# Servo.net
KiCad netlist of a schematic drawn in EAGLE
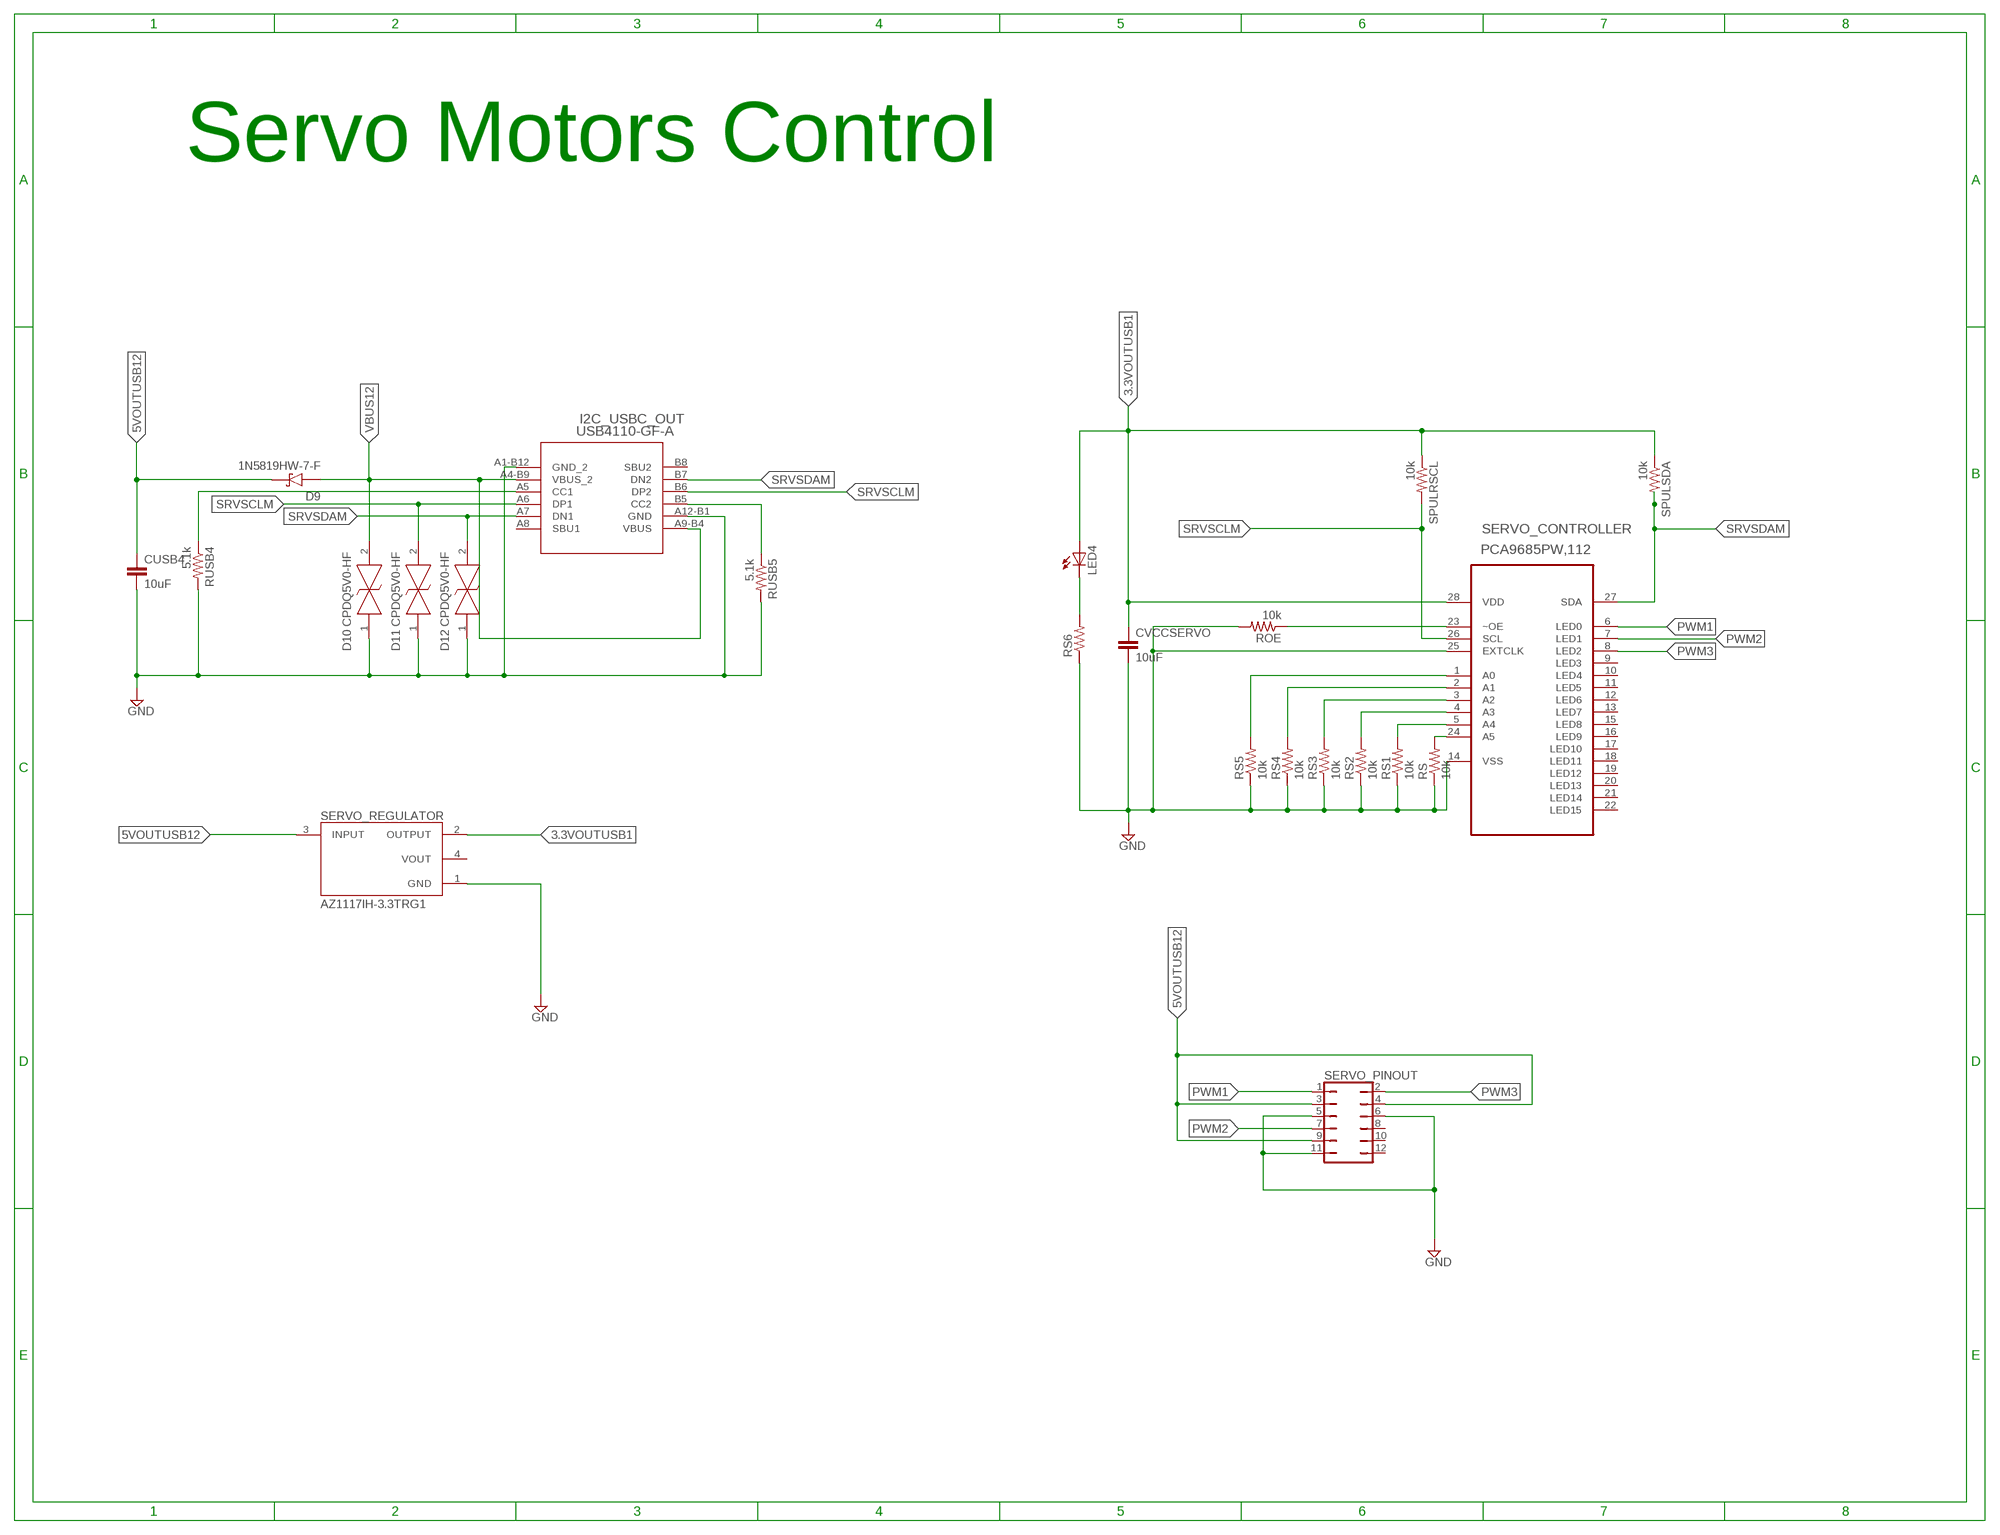
[diagram p0: schematic, sheet 1]

(export (version "E")
  (design (tool "Eeschema 10.0.6"))
  (components
    (comp (ref "CUSB4")
      (value "10uF")
      (footprint "eagle-import:C0805")
      (libsource (lib "eagle-import") (part "C-EUC0805"))
    )
    (comp (ref "CVCCSERVO")
      (value "10uF")
      (footprint "eagle-import:C0805")
      (libsource (lib "eagle-import") (part "C-EUC0805"))
    )
    (comp (ref "D9")
      (value "1N5819HW-7-F")
      (footprint "eagle-import:SOD3715X145N")
      (fields (field (name "MF") "Diodes Inc."))
      (libsource (lib "eagle-import") (part "1N5819HW-7-F"))
    )
    (comp (ref "D10")
      (value "CPDQ5V0-HF")
      (footprint "eagle-import:MBTB-D-SOD-923F-IMP-0402")
      (fields (field (name "MF") "Comchip Technology"))
      (libsource (lib "eagle-import") (part "CPDQ5V0-HF"))
    )
    (comp (ref "D11")
      (value "CPDQ5V0-HF")
      (footprint "eagle-import:MBTB-D-SOD-923F-IMP-0402")
      (fields (field (name "MF") "Comchip Technology"))
      (libsource (lib "eagle-import") (part "CPDQ5V0-HF"))
    )
    (comp (ref "D12")
      (value "CPDQ5V0-HF")
      (footprint "eagle-import:MBTB-D-SOD-923F-IMP-0402")
      (fields (field (name "MF") "Comchip Technology"))
      (libsource (lib "eagle-import") (part "CPDQ5V0-HF"))
    )
    (comp (ref "I2C_USBC_OUT")
      (value "USB4110-GF-A")
      (footprint "eagle-import:USB4110-GF-A_GCT")
      (fields (field (name "COPYRIGHT") "Copyright (C) 2023 Ultra Librarian. All rights reserved."))
      (libsource (lib "eagle-import") (part "USB4110-GF-A"))
    )
    (comp (ref "LED4")
      (value "LED")
      (footprint "eagle-import:SMARTLED-TTW")
      (libsource (lib "eagle-import") (part "LED"))
    )
    (comp (ref "ROE")
      (value "10k")
      (footprint "eagle-import:M0805")
      (libsource (lib "eagle-import") (part "R-US_M0805"))
    )
    (comp (ref "RS")
      (value "10k")
      (footprint "eagle-import:R0805")
      (libsource (lib "eagle-import") (part "R-US_R0805"))
    )
    (comp (ref "RS1")
      (value "10k")
      (footprint "eagle-import:R0805")
      (libsource (lib "eagle-import") (part "R-US_R0805"))
    )
    (comp (ref "RS2")
      (value "10k")
      (footprint "eagle-import:R0805")
      (libsource (lib "eagle-import") (part "R-US_R0805"))
    )
    (comp (ref "RS3")
      (value "10k")
      (footprint "eagle-import:R0805")
      (libsource (lib "eagle-import") (part "R-US_R0805"))
    )
    (comp (ref "RS4")
      (value "10k")
      (footprint "eagle-import:R0805")
      (libsource (lib "eagle-import") (part "R-US_R0805"))
    )
    (comp (ref "RS5")
      (value "10k")
      (footprint "eagle-import:R0805")
      (libsource (lib "eagle-import") (part "R-US_R0805"))
    )
    (comp (ref "RS6")
      (value "2.2k")
      (footprint "eagle-import:R0805")
      (libsource (lib "eagle-import") (part "R-US_R0805"))
    )
    (comp (ref "RUSB4")
      (value "5.1k")
      (footprint "eagle-import:M0805")
      (libsource (lib "eagle-import") (part "R-US_M0805"))
    )
    (comp (ref "RUSB5")
      (value "5.1k")
      (footprint "eagle-import:M0805")
      (libsource (lib "eagle-import") (part "R-US_M0805"))
    )
    (comp (ref "SERVO_CONTROLLER")
      (value "PCA9685PW,112")
      (footprint "eagle-import:SOP65P640X110-28N")
      (fields (field (name "MF") "NXP USA"))
      (libsource (lib "eagle-import") (part "PCA9685PW,112"))
    )
    (comp (ref "SERVO_PINOUT")
      (value "JP6Q")
      (footprint "eagle-import:JP6Q")
      (libsource (lib "eagle-import") (part "JP6Q"))
    )
    (comp (ref "SERVO_REGULATOR")
      (value "AZ1117IH-3.3TRG1")
      (footprint "eagle-import:SOT230P700X185-4N")
      (fields (field (name "MF") "Diodes Inc."))
      (libsource (lib "eagle-import") (part "AZ1117IH-3.3TRG1"))
    )
    (comp (ref "SPULRSCL")
      (value "10k")
      (footprint "eagle-import:M0805")
      (libsource (lib "eagle-import") (part "R-US_M0805"))
    )
    (comp (ref "SPULSDA")
      (value "10k")
      (footprint "eagle-import:M0805")
      (libsource (lib "eagle-import") (part "R-US_M0805"))
    )
  )
  (nets
    (net (code "1") (name "3.3VOUTUSB1") (class "Default")
      (node (ref "CVCCSERVO") (pin "1") (pinfunction "1_1") (pintype "passive"))
      (node (ref "LED4") (pin "A@1") (pinfunction "A_A@1") (pintype "passive"))
      (node (ref "SERVO_CONTROLLER") (pin "28") (pinfunction "VDD_28") (pintype "power_in"))
      (node (ref "SERVO_REGULATOR") (pin "2") (pinfunction "OUTPUT_2") (pintype "output"))
      (node (ref "SPULRSCL") (pin "1") (pinfunction "1_1") (pintype "passive"))
      (node (ref "SPULSDA") (pin "1") (pinfunction "1_1") (pintype "passive"))
    )
    (net (code "2") (name "5VOUTUSB12") (class "Default")
      (node (ref "CUSB4") (pin "1") (pinfunction "1_1") (pintype "passive"))
      (node (ref "D9") (pin "C") (pinfunction "K_C") (pintype "passive"))
      (node (ref "SERVO_PINOUT") (pin "3") (pinfunction "3_3") (pintype "passive"))
      (node (ref "SERVO_PINOUT") (pin "4") (pinfunction "4_4") (pintype "passive"))
      (node (ref "SERVO_PINOUT") (pin "9") (pinfunction "9_9") (pintype "passive"))
      (node (ref "SERVO_REGULATOR") (pin "3") (pinfunction "INPUT_3") (pintype "input"))
    )
    (net (code "3") (name "GND") (class "Default")
      (node (ref "CUSB4") (pin "2") (pinfunction "2_2") (pintype "passive"))
      (node (ref "CVCCSERVO") (pin "2") (pinfunction "2_2") (pintype "passive"))
      (node (ref "D10") (pin "1") (pinfunction "K_1") (pintype "bidirectional"))
      (node (ref "D11") (pin "1") (pinfunction "K_1") (pintype "bidirectional"))
      (node (ref "D12") (pin "1") (pinfunction "K_1") (pintype "bidirectional"))
      (node (ref "I2C_USBC_OUT") (pin "A1-B12") (pinfunction "GND_2_A1-B12") (pintype "passive"))
      (node (ref "I2C_USBC_OUT") (pin "A12-B1") (pinfunction "GND_A12-B1") (pintype "passive"))
      (node (ref "ROE") (pin "2") (pinfunction "2_2") (pintype "passive"))
      (node (ref "RS") (pin "1") (pinfunction "1_1") (pintype "passive"))
      (node (ref "RS1") (pin "1") (pinfunction "1_1") (pintype "passive"))
      (node (ref "RS2") (pin "1") (pinfunction "1_1") (pintype "passive"))
      (node (ref "RS3") (pin "1") (pinfunction "1_1") (pintype "passive"))
      (node (ref "RS4") (pin "1") (pinfunction "1_1") (pintype "passive"))
      (node (ref "RS5") (pin "1") (pinfunction "1_1") (pintype "passive"))
      (node (ref "RS6") (pin "1") (pinfunction "1_1") (pintype "passive"))
      (node (ref "RUSB4") (pin "2") (pinfunction "2_2") (pintype "passive"))
      (node (ref "RUSB5") (pin "2") (pinfunction "2_2") (pintype "passive"))
      (node (ref "SERVO_CONTROLLER") (pin "14") (pinfunction "VSS_14") (pintype "passive"))
      (node (ref "SERVO_CONTROLLER") (pin "25") (pinfunction "EXTCLK_25") (pintype "input"))
      (node (ref "SERVO_PINOUT") (pin "11") (pinfunction "11_11") (pintype "passive"))
      (node (ref "SERVO_PINOUT") (pin "5") (pinfunction "5_5") (pintype "passive"))
      (node (ref "SERVO_PINOUT") (pin "6") (pinfunction "6_6") (pintype "passive"))
      (node (ref "SERVO_REGULATOR") (pin "1") (pinfunction "GND_1") (pintype "power_in"))
    )
    (net (code "4") (name "Net-(I2C_USBC_OUT-CC1)") (class "Default")
      (node (ref "I2C_USBC_OUT") (pin "A5") (pinfunction "CC1_A5") (pintype "bidirectional"))
      (node (ref "RUSB4") (pin "1") (pinfunction "1_1") (pintype "passive"))
    )
    (net (code "5") (name "Net-(I2C_USBC_OUT-CC2)") (class "Default")
      (node (ref "I2C_USBC_OUT") (pin "B5") (pinfunction "CC2_B5") (pintype "bidirectional"))
      (node (ref "RUSB5") (pin "1") (pinfunction "1_1") (pintype "passive"))
    )
    (net (code "6") (name "Net-(LED4-C)") (class "Default")
      (node (ref "LED4") (pin "C@1") (pinfunction "C_C@1") (pintype "passive"))
      (node (ref "RS6") (pin "2") (pinfunction "2_2") (pintype "passive"))
    )
    (net (code "7") (name "Net-(SERVO_CONTROLLER-A0)") (class "Default")
      (node (ref "RS5") (pin "2") (pinfunction "2_2") (pintype "passive"))
      (node (ref "SERVO_CONTROLLER") (pin "1") (pinfunction "A0_1") (pintype "input"))
    )
    (net (code "8") (name "Net-(SERVO_CONTROLLER-A1)") (class "Default")
      (node (ref "RS4") (pin "2") (pinfunction "2_2") (pintype "passive"))
      (node (ref "SERVO_CONTROLLER") (pin "2") (pinfunction "A1_2") (pintype "input"))
    )
    (net (code "9") (name "Net-(SERVO_CONTROLLER-A2)") (class "Default")
      (node (ref "RS3") (pin "2") (pinfunction "2_2") (pintype "passive"))
      (node (ref "SERVO_CONTROLLER") (pin "3") (pinfunction "A2_3") (pintype "input"))
    )
    (net (code "10") (name "Net-(SERVO_CONTROLLER-A3)") (class "Default")
      (node (ref "RS2") (pin "2") (pinfunction "2_2") (pintype "passive"))
      (node (ref "SERVO_CONTROLLER") (pin "4") (pinfunction "A3_4") (pintype "input"))
    )
    (net (code "11") (name "Net-(SERVO_CONTROLLER-A4)") (class "Default")
      (node (ref "RS1") (pin "2") (pinfunction "2_2") (pintype "passive"))
      (node (ref "SERVO_CONTROLLER") (pin "5") (pinfunction "A4_5") (pintype "input"))
    )
    (net (code "12") (name "Net-(SERVO_CONTROLLER-A5)") (class "Default")
      (node (ref "RS") (pin "2") (pinfunction "2_2") (pintype "passive"))
      (node (ref "SERVO_CONTROLLER") (pin "24") (pinfunction "A5_24") (pintype "input"))
    )
    (net (code "13") (name "Net-(SERVO_CONTROLLER-~{OE})") (class "Default")
      (node (ref "ROE") (pin "1") (pinfunction "1_1") (pintype "passive"))
      (node (ref "SERVO_CONTROLLER") (pin "23") (pinfunction "~{OE}_23") (pintype "input"))
    )
    (net (code "14") (name "PWM1") (class "Default")
      (node (ref "SERVO_CONTROLLER") (pin "6") (pinfunction "LED0_6") (pintype "output"))
      (node (ref "SERVO_PINOUT") (pin "1") (pinfunction "1_1") (pintype "passive"))
    )
    (net (code "15") (name "PWM2") (class "Default")
      (node (ref "SERVO_CONTROLLER") (pin "7") (pinfunction "LED1_7") (pintype "output"))
      (node (ref "SERVO_PINOUT") (pin "7") (pinfunction "7_7") (pintype "passive"))
    )
    (net (code "16") (name "PWM3") (class "Default")
      (node (ref "SERVO_CONTROLLER") (pin "8") (pinfunction "LED2_8") (pintype "output"))
      (node (ref "SERVO_PINOUT") (pin "2") (pinfunction "2_2") (pintype "passive"))
    )
    (net (code "17") (name "SRVSCLM") (class "Default")
      (node (ref "D11") (pin "2") (pinfunction "A_2") (pintype "bidirectional"))
      (node (ref "I2C_USBC_OUT") (pin "A6") (pinfunction "DP1_A6") (pintype "bidirectional"))
      (node (ref "I2C_USBC_OUT") (pin "B6") (pinfunction "DP2_B6") (pintype "bidirectional"))
      (node (ref "SERVO_CONTROLLER") (pin "26") (pinfunction "SCL_26") (pintype "input"))
      (node (ref "SPULRSCL") (pin "2") (pinfunction "2_2") (pintype "passive"))
    )
    (net (code "18") (name "SRVSDAM") (class "Default")
      (node (ref "D12") (pin "2") (pinfunction "A_2") (pintype "bidirectional"))
      (node (ref "I2C_USBC_OUT") (pin "A7") (pinfunction "DN1_A7") (pintype "bidirectional"))
      (node (ref "I2C_USBC_OUT") (pin "B7") (pinfunction "DN2_B7") (pintype "bidirectional"))
      (node (ref "SERVO_CONTROLLER") (pin "27") (pinfunction "SDA_27") (pintype "bidirectional"))
      (node (ref "SPULSDA") (pin "2") (pinfunction "2_2") (pintype "passive"))
    )
    (net (code "19") (name "VBUS12") (class "Default")
      (node (ref "D10") (pin "2") (pinfunction "A_2") (pintype "bidirectional"))
      (node (ref "D9") (pin "A") (pinfunction "A_A") (pintype "passive"))
      (node (ref "I2C_USBC_OUT") (pin "A4-B9") (pinfunction "VBUS_2_A4-B9") (pintype "power_in"))
      (node (ref "I2C_USBC_OUT") (pin "A9-B4") (pinfunction "VBUS_A9-B4") (pintype "power_in"))
    )
    (net (code "20") (name "unconnected-(I2C_USBC_OUT-SBU1-PadA8)") (class "Default")
      (node (ref "I2C_USBC_OUT") (pin "A8") (pinfunction "SBU1_A8") (pintype "bidirectional"))
    )
    (net (code "21") (name "unconnected-(I2C_USBC_OUT-SBU2-PadB8)") (class "Default")
      (node (ref "I2C_USBC_OUT") (pin "B8") (pinfunction "SBU2_B8") (pintype "bidirectional"))
    )
    (net (code "22") (name "unconnected-(SERVO_CONTROLLER-LED3-Pad9)") (class "Default")
      (node (ref "SERVO_CONTROLLER") (pin "9") (pinfunction "LED3_9") (pintype "output"))
    )
    (net (code "23") (name "unconnected-(SERVO_CONTROLLER-LED4-Pad10)") (class "Default")
      (node (ref "SERVO_CONTROLLER") (pin "10") (pinfunction "LED4_10") (pintype "output"))
    )
    (net (code "24") (name "unconnected-(SERVO_CONTROLLER-LED5-Pad11)") (class "Default")
      (node (ref "SERVO_CONTROLLER") (pin "11") (pinfunction "LED5_11") (pintype "output"))
    )
    (net (code "25") (name "unconnected-(SERVO_CONTROLLER-LED6-Pad12)") (class "Default")
      (node (ref "SERVO_CONTROLLER") (pin "12") (pinfunction "LED6_12") (pintype "output"))
    )
    (net (code "26") (name "unconnected-(SERVO_CONTROLLER-LED7-Pad13)") (class "Default")
      (node (ref "SERVO_CONTROLLER") (pin "13") (pinfunction "LED7_13") (pintype "output"))
    )
    (net (code "27") (name "unconnected-(SERVO_CONTROLLER-LED8-Pad15)") (class "Default")
      (node (ref "SERVO_CONTROLLER") (pin "15") (pinfunction "LED8_15") (pintype "output"))
    )
    (net (code "28") (name "unconnected-(SERVO_CONTROLLER-LED9-Pad16)") (class "Default")
      (node (ref "SERVO_CONTROLLER") (pin "16") (pinfunction "LED9_16") (pintype "output"))
    )
    (net (code "29") (name "unconnected-(SERVO_CONTROLLER-LED10-Pad17)") (class "Default")
      (node (ref "SERVO_CONTROLLER") (pin "17") (pinfunction "LED10_17") (pintype "output"))
    )
    (net (code "30") (name "unconnected-(SERVO_CONTROLLER-LED11-Pad18)") (class "Default")
      (node (ref "SERVO_CONTROLLER") (pin "18") (pinfunction "LED11_18") (pintype "output"))
    )
    (net (code "31") (name "unconnected-(SERVO_CONTROLLER-LED12-Pad19)") (class "Default")
      (node (ref "SERVO_CONTROLLER") (pin "19") (pinfunction "LED12_19") (pintype "output"))
    )
    (net (code "32") (name "unconnected-(SERVO_CONTROLLER-LED13-Pad20)") (class "Default")
      (node (ref "SERVO_CONTROLLER") (pin "20") (pinfunction "LED13_20") (pintype "output"))
    )
    (net (code "33") (name "unconnected-(SERVO_CONTROLLER-LED14-Pad21)") (class "Default")
      (node (ref "SERVO_CONTROLLER") (pin "21") (pinfunction "LED14_21") (pintype "output"))
    )
    (net (code "34") (name "unconnected-(SERVO_CONTROLLER-LED15-Pad22)") (class "Default")
      (node (ref "SERVO_CONTROLLER") (pin "22") (pinfunction "LED15_22") (pintype "output"))
    )
    (net (code "35") (name "unconnected-(SERVO_PINOUT-Pad8)") (class "Default")
      (node (ref "SERVO_PINOUT") (pin "8") (pinfunction "8_8") (pintype "passive"))
    )
    (net (code "36") (name "unconnected-(SERVO_PINOUT-Pad10)") (class "Default")
      (node (ref "SERVO_PINOUT") (pin "10") (pinfunction "10_10") (pintype "passive"))
    )
    (net (code "37") (name "unconnected-(SERVO_PINOUT-Pad12)") (class "Default")
      (node (ref "SERVO_PINOUT") (pin "12") (pinfunction "12_12") (pintype "passive"))
    )
    (net (code "38") (name "unconnected-(SERVO_REGULATOR-VOUT-Pad4)") (class "Default")
      (node (ref "SERVO_REGULATOR") (pin "4") (pinfunction "VOUT_4") (pintype "output"))
    )
  )
)
